# fx3_b.net
KiCad netlist of a schematic drawn in Altium Designer
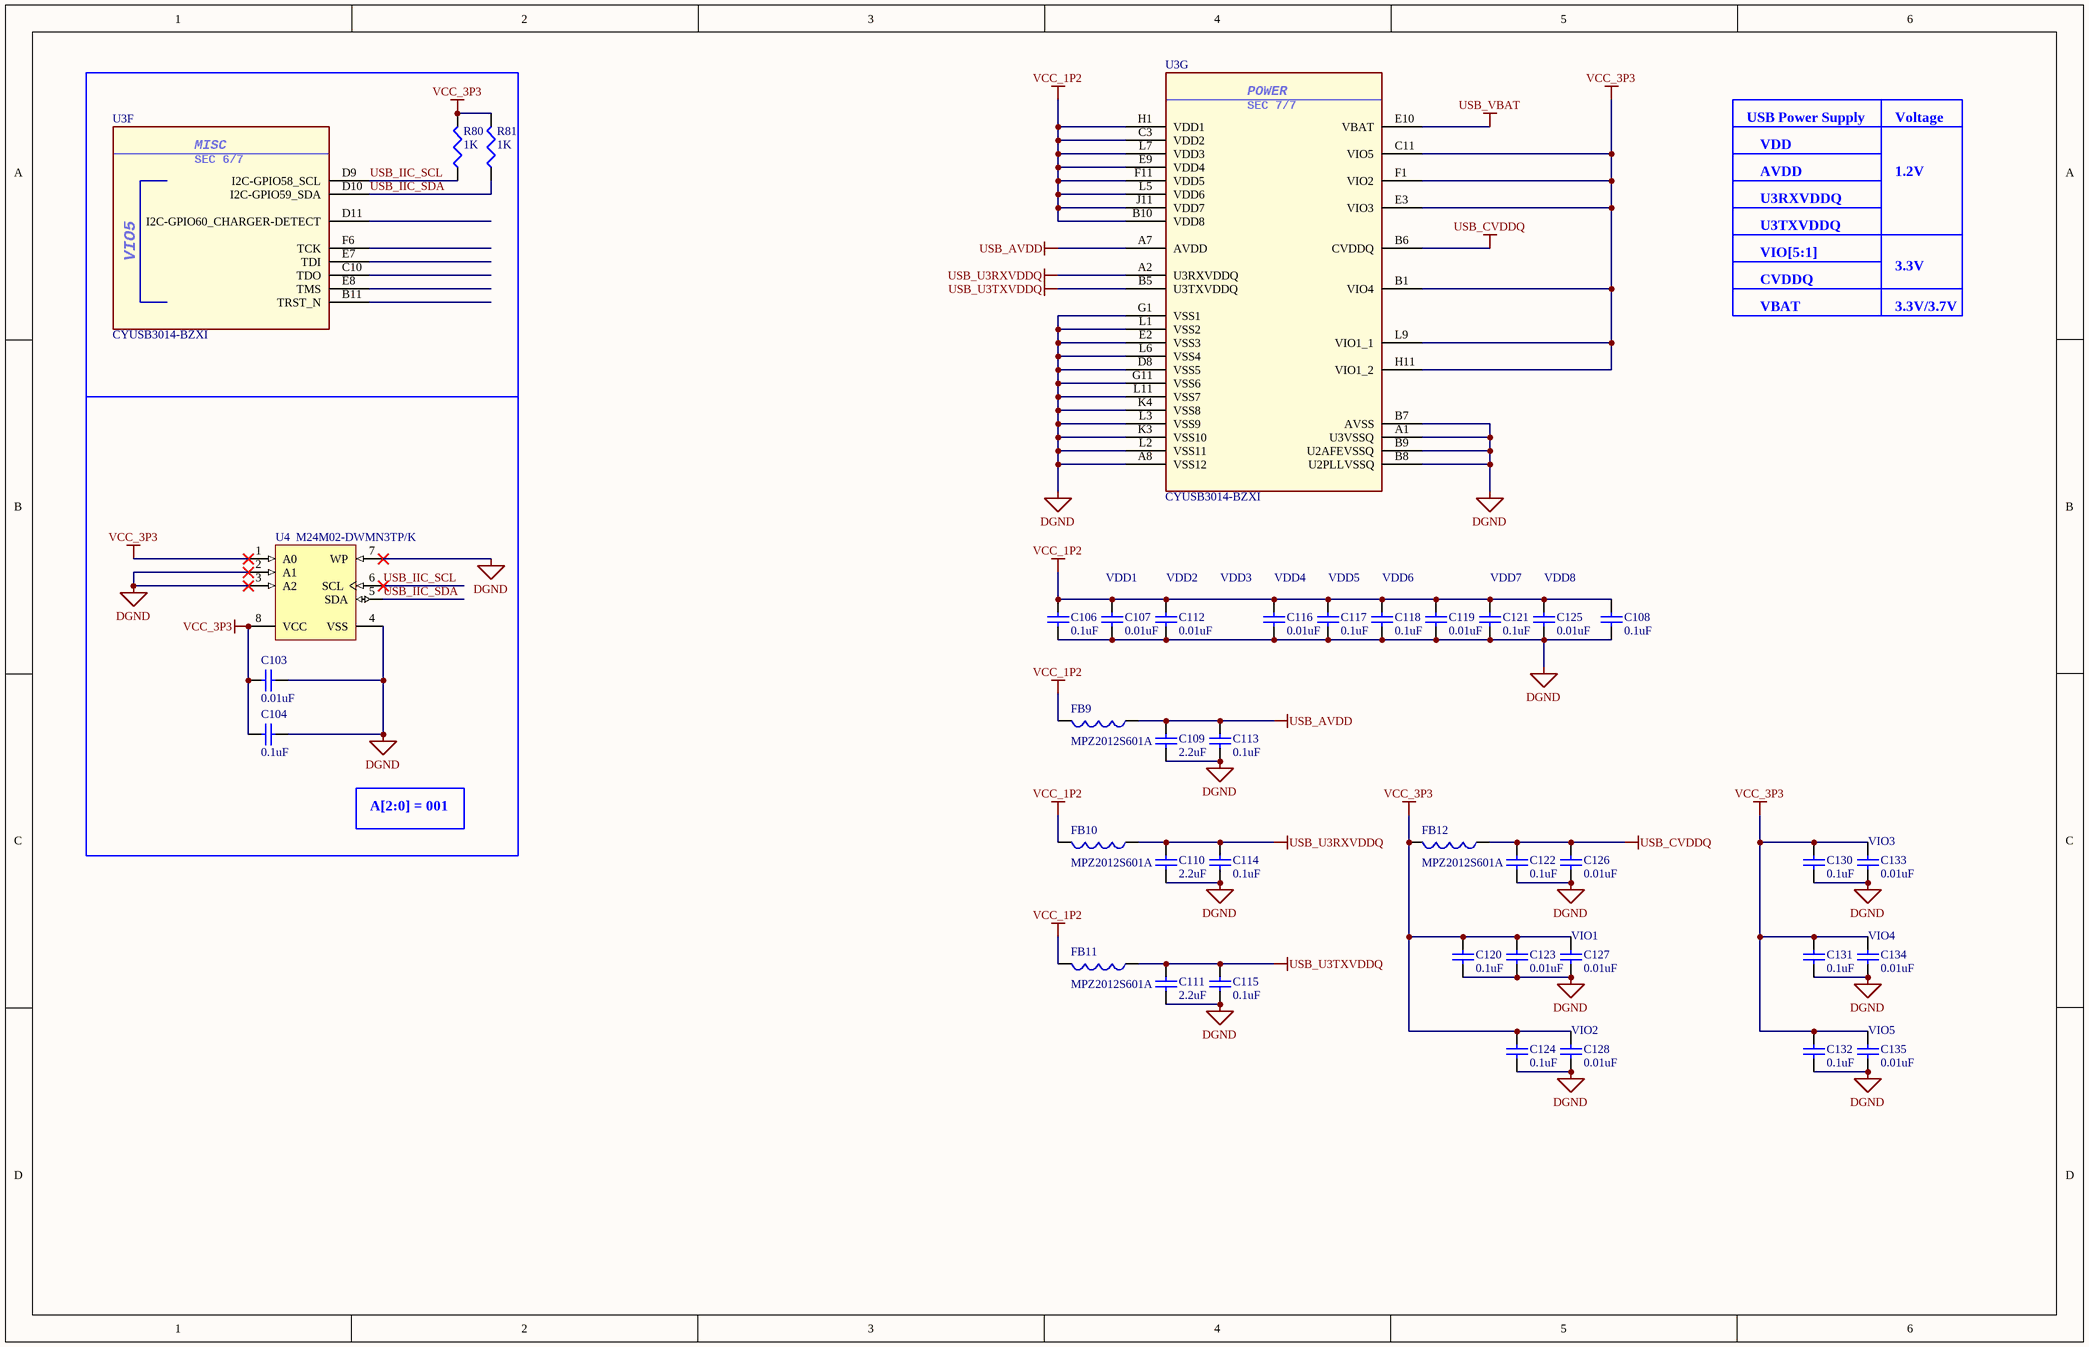
[diagram p0: fx3_b.SchDoc]

(export (version "E")
  (design (tool "Eeschema 10.0.6"))
  (components
    (comp (ref "C103")
      (value "0.01uF")
      (footprint "C_0402")
      (description "Capacitor (Semiconductor SIM Model)")
      (fields (field (name "Comment") "Capacitor") (field (name "PUBLISHER") "Altium Limited"))
      (libsource (lib "Miscellaneous Devices") (part "Cap Semi"))
    )
    (comp (ref "C104")
      (value "0.1uF")
      (footprint "C_0402")
      (description "Capacitor (Semiconductor SIM Model)")
      (fields (field (name "Comment") "Capacitor") (field (name "PUBLISHER") "Altium Limited"))
      (libsource (lib "Miscellaneous Devices") (part "Cap Semi"))
    )
    (comp (ref "C106")
      (value "0.1uF")
      (footprint "C_0402")
      (description "Capacitor (Semiconductor SIM Model)")
      (fields (field (name "Comment") "Capacitor") (field (name "PUBLISHER") "Altium Limited"))
      (libsource (lib "Miscellaneous Devices") (part "Cap Semi"))
    )
    (comp (ref "C107")
      (value "0.01uF")
      (footprint "C_0402")
      (description "Capacitor (Semiconductor SIM Model)")
      (fields (field (name "Comment") "Capacitor") (field (name "PUBLISHER") "Altium Limited"))
      (libsource (lib "Miscellaneous Devices") (part "Cap Semi"))
    )
    (comp (ref "C108")
      (value "0.1uF")
      (footprint "C_0402")
      (description "Capacitor (Semiconductor SIM Model)")
      (fields (field (name "Comment") "Capacitor") (field (name "PUBLISHER") "Altium Limited"))
      (libsource (lib "Miscellaneous Devices") (part "Cap Semi"))
    )
    (comp (ref "C109")
      (value "2.2uF")
      (footprint "C_0402")
      (description "Capacitor (Semiconductor SIM Model)")
      (fields (field (name "Comment") "Capacitor") (field (name "PUBLISHER") "Altium Limited"))
      (libsource (lib "Miscellaneous Devices") (part "Cap Semi"))
    )
    (comp (ref "C110")
      (value "2.2uF")
      (footprint "C_0402")
      (description "Capacitor (Semiconductor SIM Model)")
      (fields (field (name "Comment") "Capacitor") (field (name "PUBLISHER") "Altium Limited"))
      (libsource (lib "Miscellaneous Devices") (part "Cap Semi"))
    )
    (comp (ref "C111")
      (value "2.2uF")
      (footprint "C_0402")
      (description "Capacitor (Semiconductor SIM Model)")
      (fields (field (name "Comment") "Capacitor") (field (name "PUBLISHER") "Altium Limited"))
      (libsource (lib "Miscellaneous Devices") (part "Cap Semi"))
    )
    (comp (ref "C112")
      (value "0.01uF")
      (footprint "C_0402")
      (description "Capacitor (Semiconductor SIM Model)")
      (fields (field (name "Comment") "Capacitor") (field (name "PUBLISHER") "Altium Limited"))
      (libsource (lib "Miscellaneous Devices") (part "Cap Semi"))
    )
    (comp (ref "C113")
      (value "0.1uF")
      (footprint "C_0402")
      (description "Capacitor (Semiconductor SIM Model)")
      (fields (field (name "Comment") "Capacitor") (field (name "PUBLISHER") "Altium Limited"))
      (libsource (lib "Miscellaneous Devices") (part "Cap Semi"))
    )
    (comp (ref "C114")
      (value "0.1uF")
      (footprint "C_0402")
      (description "Capacitor (Semiconductor SIM Model)")
      (fields (field (name "Comment") "Capacitor") (field (name "PUBLISHER") "Altium Limited"))
      (libsource (lib "Miscellaneous Devices") (part "Cap Semi"))
    )
    (comp (ref "C115")
      (value "0.1uF")
      (footprint "C_0402")
      (description "Capacitor (Semiconductor SIM Model)")
      (fields (field (name "Comment") "Capacitor") (field (name "PUBLISHER") "Altium Limited"))
      (libsource (lib "Miscellaneous Devices") (part "Cap Semi"))
    )
    (comp (ref "C116")
      (value "0.01uF")
      (footprint "C_0402")
      (description "Capacitor (Semiconductor SIM Model)")
      (fields (field (name "Comment") "Capacitor") (field (name "PUBLISHER") "Altium Limited"))
      (libsource (lib "Miscellaneous Devices") (part "Cap Semi"))
    )
    (comp (ref "C117")
      (value "0.1uF")
      (footprint "C_0402")
      (description "Capacitor (Semiconductor SIM Model)")
      (fields (field (name "Comment") "Capacitor") (field (name "PUBLISHER") "Altium Limited"))
      (libsource (lib "Miscellaneous Devices") (part "Cap Semi"))
    )
    (comp (ref "C118")
      (value "0.1uF")
      (footprint "C_0402")
      (description "Capacitor (Semiconductor SIM Model)")
      (fields (field (name "Comment") "Capacitor") (field (name "PUBLISHER") "Altium Limited"))
      (libsource (lib "Miscellaneous Devices") (part "Cap Semi"))
    )
    (comp (ref "C119")
      (value "0.01uF")
      (footprint "C_0402")
      (description "Capacitor (Semiconductor SIM Model)")
      (fields (field (name "Comment") "Capacitor") (field (name "PUBLISHER") "Altium Limited"))
      (libsource (lib "Miscellaneous Devices") (part "Cap Semi"))
    )
    (comp (ref "C120")
      (value "0.1uF")
      (footprint "C_0402")
      (description "Capacitor (Semiconductor SIM Model)")
      (fields (field (name "Comment") "Capacitor") (field (name "PUBLISHER") "Altium Limited"))
      (libsource (lib "Miscellaneous Devices") (part "Cap Semi"))
    )
    (comp (ref "C121")
      (value "0.1uF")
      (footprint "C_0402")
      (description "Capacitor (Semiconductor SIM Model)")
      (fields (field (name "Comment") "Capacitor") (field (name "PUBLISHER") "Altium Limited"))
      (libsource (lib "Miscellaneous Devices") (part "Cap Semi"))
    )
    (comp (ref "C122")
      (value "0.1uF")
      (footprint "C_0402")
      (description "Capacitor (Semiconductor SIM Model)")
      (fields (field (name "Comment") "Capacitor") (field (name "PUBLISHER") "Altium Limited"))
      (libsource (lib "Miscellaneous Devices") (part "Cap Semi"))
    )
    (comp (ref "C123")
      (value "0.01uF")
      (footprint "C_0402")
      (description "Capacitor (Semiconductor SIM Model)")
      (fields (field (name "Comment") "Capacitor") (field (name "PUBLISHER") "Altium Limited"))
      (libsource (lib "Miscellaneous Devices") (part "Cap Semi"))
    )
    (comp (ref "C124")
      (value "0.1uF")
      (footprint "C_0402")
      (description "Capacitor (Semiconductor SIM Model)")
      (fields (field (name "Comment") "Capacitor") (field (name "PUBLISHER") "Altium Limited"))
      (libsource (lib "Miscellaneous Devices") (part "Cap Semi"))
    )
    (comp (ref "C125")
      (value "0.01uF")
      (footprint "C_0402")
      (description "Capacitor (Semiconductor SIM Model)")
      (fields (field (name "Comment") "Capacitor") (field (name "PUBLISHER") "Altium Limited"))
      (libsource (lib "Miscellaneous Devices") (part "Cap Semi"))
    )
    (comp (ref "C126")
      (value "0.01uF")
      (footprint "C_0402")
      (description "Capacitor (Semiconductor SIM Model)")
      (fields (field (name "Comment") "Capacitor") (field (name "PUBLISHER") "Altium Limited"))
      (libsource (lib "Miscellaneous Devices") (part "Cap Semi"))
    )
    (comp (ref "C127")
      (value "0.01uF")
      (footprint "C_0402")
      (description "Capacitor (Semiconductor SIM Model)")
      (fields (field (name "Comment") "Capacitor") (field (name "PUBLISHER") "Altium Limited"))
      (libsource (lib "Miscellaneous Devices") (part "Cap Semi"))
    )
    (comp (ref "C128")
      (value "0.01uF")
      (footprint "C_0402")
      (description "Capacitor (Semiconductor SIM Model)")
      (fields (field (name "Comment") "Capacitor") (field (name "PUBLISHER") "Altium Limited"))
      (libsource (lib "Miscellaneous Devices") (part "Cap Semi"))
    )
    (comp (ref "C130")
      (value "0.1uF")
      (footprint "C_0402")
      (description "Capacitor (Semiconductor SIM Model)")
      (fields (field (name "Comment") "Capacitor") (field (name "PUBLISHER") "Altium Limited"))
      (libsource (lib "Miscellaneous Devices") (part "Cap Semi"))
    )
    (comp (ref "C131")
      (value "0.1uF")
      (footprint "C_0402")
      (description "Capacitor (Semiconductor SIM Model)")
      (fields (field (name "Comment") "Capacitor") (field (name "PUBLISHER") "Altium Limited"))
      (libsource (lib "Miscellaneous Devices") (part "Cap Semi"))
    )
    (comp (ref "C132")
      (value "0.1uF")
      (footprint "C_0402")
      (description "Capacitor (Semiconductor SIM Model)")
      (fields (field (name "Comment") "Capacitor") (field (name "PUBLISHER") "Altium Limited"))
      (libsource (lib "Miscellaneous Devices") (part "Cap Semi"))
    )
    (comp (ref "C133")
      (value "0.01uF")
      (footprint "C_0402")
      (description "Capacitor (Semiconductor SIM Model)")
      (fields (field (name "Comment") "Capacitor") (field (name "PUBLISHER") "Altium Limited"))
      (libsource (lib "Miscellaneous Devices") (part "Cap Semi"))
    )
    (comp (ref "C134")
      (value "0.01uF")
      (footprint "C_0402")
      (description "Capacitor (Semiconductor SIM Model)")
      (fields (field (name "Comment") "Capacitor") (field (name "PUBLISHER") "Altium Limited"))
      (libsource (lib "Miscellaneous Devices") (part "Cap Semi"))
    )
    (comp (ref "C135")
      (value "0.01uF")
      (footprint "C_0402")
      (description "Capacitor (Semiconductor SIM Model)")
      (fields (field (name "Comment") "Capacitor") (field (name "PUBLISHER") "Altium Limited"))
      (libsource (lib "Miscellaneous Devices") (part "Cap Semi"))
    )
    (comp (ref "FB9")
      (value "MPZ2012S601A")
      (footprint "SMD_0805")
      (description "MPZ2012X")
      (libsource (lib "clc_ad_pro") (part "MPZ2012X"))
    )
    (comp (ref "FB10")
      (value "MPZ2012S601A")
      (footprint "SMD_0805")
      (description "MPZ2012X")
      (libsource (lib "clc_ad_pro") (part "MPZ2012X"))
    )
    (comp (ref "FB11")
      (value "MPZ2012S601A")
      (footprint "SMD_0805")
      (description "MPZ2012X")
      (libsource (lib "clc_ad_pro") (part "MPZ2012X"))
    )
    (comp (ref "FB12")
      (value "MPZ2012S601A")
      (footprint "SMD_0805")
      (description "MPZ2012X")
      (libsource (lib "clc_ad_pro") (part "MPZ2012X"))
    )
    (comp (ref "R80")
      (value "1K")
      (footprint "J1-0603")
      (description "Resistor")
      (fields (field (name "PUBLISHER") "Altium Limited"))
      (libsource (lib "Miscellaneous Devices") (part "Res3"))
    )
    (comp (ref "R81")
      (value "1K")
      (footprint "J1-0603")
      (description "Resistor")
      (fields (field (name "PUBLISHER") "Altium Limited"))
      (libsource (lib "Miscellaneous Devices") (part "Res3"))
    )
    (comp (ref "U3")
      (value "CYUSB3014-BZXI")
      (footprint "CYUSB301X_BGA121x11")
      (description "FX3 CYUSB3014")
      (libsource (lib "apex_usb_v2") (part "CYUSB30XX"))
    )
    (comp (ref "U4")
      (value "M24M02-DWMN3TP/K")
      (footprint "SOIC-SN8_N")
      (description "256Kbit, 400kHz, 2.5V, I2C Serial EEPROM, 8-Pin SOIC 150mil, Industrial Temperature")
      (fields (field (name "MANUFACTURER") "Microchip") (field (name "PARTNUMBER") "24LC256-I/SN"))
      (libsource (lib "Microchip I2C Serial EEPROM") (part "24LC256-I/SN"))
    )
  )
  (nets
    (net (code "1") (name "/USB_IIC_SCL") (class "Default")
      (node (ref "R80") (pin "1") (pinfunction "1_1") (pintype "passive"))
      (node (ref "U3") (pin "D9") (pinfunction "I2C-GPIO58_SCL_D9") (pintype "passive"))
      (node (ref "U4") (pin "6") (pinfunction "SCL_6") (pintype "input"))
    )
    (net (code "2") (name "/USB_IIC_SDA") (class "Default")
      (node (ref "R81") (pin "1") (pinfunction "1_1") (pintype "passive"))
      (node (ref "U3") (pin "D10") (pinfunction "I2C-GPIO59_SDA_D10") (pintype "passive"))
      (node (ref "U4") (pin "5") (pinfunction "SDA_5") (pintype "bidirectional"))
    )
    (net (code "3") (name "DGND") (class "Default")
      (node (ref "C103") (pin "2") (pinfunction "2_2") (pintype "passive"))
      (node (ref "C104") (pin "2") (pinfunction "2_2") (pintype "passive"))
      (node (ref "C106") (pin "2") (pinfunction "2_2") (pintype "passive"))
      (node (ref "C107") (pin "2") (pinfunction "2_2") (pintype "passive"))
      (node (ref "C108") (pin "2") (pinfunction "2_2") (pintype "passive"))
      (node (ref "C109") (pin "2") (pinfunction "2_2") (pintype "passive"))
      (node (ref "C110") (pin "2") (pinfunction "2_2") (pintype "passive"))
      (node (ref "C111") (pin "2") (pinfunction "2_2") (pintype "passive"))
      (node (ref "C112") (pin "2") (pinfunction "2_2") (pintype "passive"))
      (node (ref "C113") (pin "2") (pinfunction "2_2") (pintype "passive"))
      (node (ref "C114") (pin "2") (pinfunction "2_2") (pintype "passive"))
      (node (ref "C115") (pin "2") (pinfunction "2_2") (pintype "passive"))
      (node (ref "C116") (pin "2") (pinfunction "2_2") (pintype "passive"))
      (node (ref "C117") (pin "2") (pinfunction "2_2") (pintype "passive"))
      (node (ref "C118") (pin "2") (pinfunction "2_2") (pintype "passive"))
      (node (ref "C119") (pin "2") (pinfunction "2_2") (pintype "passive"))
      (node (ref "C120") (pin "2") (pinfunction "2_2") (pintype "passive"))
      (node (ref "C121") (pin "2") (pinfunction "2_2") (pintype "passive"))
      (node (ref "C122") (pin "2") (pinfunction "2_2") (pintype "passive"))
      (node (ref "C123") (pin "2") (pinfunction "2_2") (pintype "passive"))
      (node (ref "C124") (pin "2") (pinfunction "2_2") (pintype "passive"))
      (node (ref "C125") (pin "2") (pinfunction "2_2") (pintype "passive"))
      (node (ref "C126") (pin "2") (pinfunction "2_2") (pintype "passive"))
      (node (ref "C127") (pin "2") (pinfunction "2_2") (pintype "passive"))
      (node (ref "C128") (pin "2") (pinfunction "2_2") (pintype "passive"))
      (node (ref "C130") (pin "2") (pinfunction "2_2") (pintype "passive"))
      (node (ref "C131") (pin "2") (pinfunction "2_2") (pintype "passive"))
      (node (ref "C132") (pin "2") (pinfunction "2_2") (pintype "passive"))
      (node (ref "C133") (pin "2") (pinfunction "2_2") (pintype "passive"))
      (node (ref "C134") (pin "2") (pinfunction "2_2") (pintype "passive"))
      (node (ref "C135") (pin "2") (pinfunction "2_2") (pintype "passive"))
      (node (ref "U3") (pin "A1") (pinfunction "U3VSSQ_A1") (pintype "passive"))
      (node (ref "U3") (pin "A8") (pinfunction "VSS12_A8") (pintype "passive"))
      (node (ref "U3") (pin "B7") (pinfunction "AVSS_B7") (pintype "passive"))
      (node (ref "U3") (pin "B8") (pinfunction "U2PLLVSSQ_B8") (pintype "passive"))
      (node (ref "U3") (pin "B9") (pinfunction "U2AFEVSSQ_B9") (pintype "passive"))
      (node (ref "U3") (pin "D8") (pinfunction "VSS5_D8") (pintype "passive"))
      (node (ref "U3") (pin "E2") (pinfunction "VSS3_E2") (pintype "passive"))
      (node (ref "U3") (pin "G1") (pinfunction "VSS1_G1") (pintype "passive"))
      (node (ref "U3") (pin "G11") (pinfunction "VSS6_G11") (pintype "passive"))
      (node (ref "U3") (pin "K3") (pinfunction "VSS10_K3") (pintype "passive"))
      (node (ref "U3") (pin "K4") (pinfunction "VSS8_K4") (pintype "passive"))
      (node (ref "U3") (pin "L1") (pinfunction "VSS2_L1") (pintype "passive"))
      (node (ref "U3") (pin "L11") (pinfunction "VSS7_L11") (pintype "passive"))
      (node (ref "U3") (pin "L2") (pinfunction "VSS11_L2") (pintype "passive"))
      (node (ref "U3") (pin "L3") (pinfunction "VSS9_L3") (pintype "passive"))
      (node (ref "U3") (pin "L6") (pinfunction "VSS4_L6") (pintype "passive"))
      (node (ref "U4") (pin "2") (pinfunction "A1_2") (pintype "input"))
      (node (ref "U4") (pin "3") (pinfunction "A2_3") (pintype "input"))
      (node (ref "U4") (pin "4") (pinfunction "VSS_4") (pintype "power_in"))
      (node (ref "U4") (pin "7") (pinfunction "WP_7") (pintype "input"))
    )
    (net (code "4") (name "USB_AVDD") (class "Default")
      (node (ref "C109") (pin "1") (pinfunction "1_1") (pintype "passive"))
      (node (ref "C113") (pin "1") (pinfunction "1_1") (pintype "passive"))
      (node (ref "FB9") (pin "1") (pinfunction "1_1") (pintype "passive"))
      (node (ref "U3") (pin "A7") (pinfunction "AVDD_A7") (pintype "passive"))
    )
    (net (code "5") (name "USB_CVDDQ") (class "Default")
      (node (ref "C122") (pin "1") (pinfunction "1_1") (pintype "passive"))
      (node (ref "C126") (pin "1") (pinfunction "1_1") (pintype "passive"))
      (node (ref "FB12") (pin "1") (pinfunction "1_1") (pintype "passive"))
      (node (ref "U3") (pin "B6") (pinfunction "CVDDQ_B6") (pintype "passive"))
    )
    (net (code "6") (name "USB_U3RXVDDQ") (class "Default")
      (node (ref "C110") (pin "1") (pinfunction "1_1") (pintype "passive"))
      (node (ref "C114") (pin "1") (pinfunction "1_1") (pintype "passive"))
      (node (ref "FB10") (pin "1") (pinfunction "1_1") (pintype "passive"))
      (node (ref "U3") (pin "A2") (pinfunction "U3RXVDDQ_A2") (pintype "passive"))
    )
    (net (code "7") (name "USB_U3TXVDDQ") (class "Default")
      (node (ref "C111") (pin "1") (pinfunction "1_1") (pintype "passive"))
      (node (ref "C115") (pin "1") (pinfunction "1_1") (pintype "passive"))
      (node (ref "FB11") (pin "1") (pinfunction "1_1") (pintype "passive"))
      (node (ref "U3") (pin "B5") (pinfunction "U3TXVDDQ_B5") (pintype "passive"))
    )
    (net (code "8") (name "USB_VBAT") (class "Default")
      (node (ref "U3") (pin "E10") (pinfunction "VBAT_E10") (pintype "passive"))
    )
    (net (code "9") (name "VCC_1P2") (class "Default")
      (node (ref "C106") (pin "1") (pinfunction "1_1") (pintype "passive"))
      (node (ref "C107") (pin "1") (pinfunction "1_1") (pintype "passive"))
      (node (ref "C108") (pin "1") (pinfunction "1_1") (pintype "passive"))
      (node (ref "C112") (pin "1") (pinfunction "1_1") (pintype "passive"))
      (node (ref "C116") (pin "1") (pinfunction "1_1") (pintype "passive"))
      (node (ref "C117") (pin "1") (pinfunction "1_1") (pintype "passive"))
      (node (ref "C118") (pin "1") (pinfunction "1_1") (pintype "passive"))
      (node (ref "C119") (pin "1") (pinfunction "1_1") (pintype "passive"))
      (node (ref "C121") (pin "1") (pinfunction "1_1") (pintype "passive"))
      (node (ref "C125") (pin "1") (pinfunction "1_1") (pintype "passive"))
      (node (ref "FB10") (pin "2") (pinfunction "2_2") (pintype "passive"))
      (node (ref "FB11") (pin "2") (pinfunction "2_2") (pintype "passive"))
      (node (ref "FB9") (pin "2") (pinfunction "2_2") (pintype "passive"))
      (node (ref "U3") (pin "B10") (pinfunction "VDD8_B10") (pintype "passive"))
      (node (ref "U3") (pin "C3") (pinfunction "VDD2_C3") (pintype "passive"))
      (node (ref "U3") (pin "E9") (pinfunction "VDD4_E9") (pintype "passive"))
      (node (ref "U3") (pin "F11") (pinfunction "VDD5_F11") (pintype "passive"))
      (node (ref "U3") (pin "H1") (pinfunction "VDD1_H1") (pintype "passive"))
      (node (ref "U3") (pin "J11") (pinfunction "VDD7_J11") (pintype "passive"))
      (node (ref "U3") (pin "L5") (pinfunction "VDD6_L5") (pintype "passive"))
      (node (ref "U3") (pin "L7") (pinfunction "VDD3_L7") (pintype "passive"))
    )
    (net (code "10") (name "VCC_3P3") (class "Default")
      (node (ref "C103") (pin "1") (pinfunction "1_1") (pintype "passive"))
      (node (ref "C104") (pin "1") (pinfunction "1_1") (pintype "passive"))
      (node (ref "C120") (pin "1") (pinfunction "1_1") (pintype "passive"))
      (node (ref "C123") (pin "1") (pinfunction "1_1") (pintype "passive"))
      (node (ref "C124") (pin "1") (pinfunction "1_1") (pintype "passive"))
      (node (ref "C127") (pin "1") (pinfunction "1_1") (pintype "passive"))
      (node (ref "C128") (pin "1") (pinfunction "1_1") (pintype "passive"))
      (node (ref "C130") (pin "1") (pinfunction "1_1") (pintype "passive"))
      (node (ref "C131") (pin "1") (pinfunction "1_1") (pintype "passive"))
      (node (ref "C132") (pin "1") (pinfunction "1_1") (pintype "passive"))
      (node (ref "C133") (pin "1") (pinfunction "1_1") (pintype "passive"))
      (node (ref "C134") (pin "1") (pinfunction "1_1") (pintype "passive"))
      (node (ref "C135") (pin "1") (pinfunction "1_1") (pintype "passive"))
      (node (ref "FB12") (pin "2") (pinfunction "2_2") (pintype "passive"))
      (node (ref "R80") (pin "2") (pinfunction "2_2") (pintype "passive"))
      (node (ref "R81") (pin "2") (pinfunction "2_2") (pintype "passive"))
      (node (ref "U3") (pin "B1") (pinfunction "VIO4_B1") (pintype "passive"))
      (node (ref "U3") (pin "C11") (pinfunction "VIO5_C11") (pintype "passive"))
      (node (ref "U3") (pin "E3") (pinfunction "VIO3_E3") (pintype "passive"))
      (node (ref "U3") (pin "F1") (pinfunction "VIO2_F1") (pintype "passive"))
      (node (ref "U3") (pin "H11") (pinfunction "VIO1_2_H11") (pintype "passive"))
      (node (ref "U3") (pin "L9") (pinfunction "VIO1_1_L9") (pintype "passive"))
      (node (ref "U4") (pin "1") (pinfunction "A0_1") (pintype "input"))
      (node (ref "U4") (pin "8") (pinfunction "VCC_8") (pintype "power_in"))
    )
    (net (code "11") (name "unconnected-(U3F-I2C-GPIO60_CHARGER-DETECT-PadD11)") (class "Default")
      (node (ref "U3") (pin "D11") (pinfunction "I2C-GPIO60_CHARGER-DETECT_D11") (pintype "passive"))
    )
    (net (code "12") (name "unconnected-(U3F-TCK-PadF6)") (class "Default")
      (node (ref "U3") (pin "F6") (pinfunction "TCK_F6") (pintype "passive"))
    )
    (net (code "13") (name "unconnected-(U3F-TDI-PadE7)") (class "Default")
      (node (ref "U3") (pin "E7") (pinfunction "TDI_E7") (pintype "passive"))
    )
    (net (code "14") (name "unconnected-(U3F-TDO-PadC10)") (class "Default")
      (node (ref "U3") (pin "C10") (pinfunction "TDO_C10") (pintype "passive"))
    )
    (net (code "15") (name "unconnected-(U3F-TMS-PadE8)") (class "Default")
      (node (ref "U3") (pin "E8") (pinfunction "TMS_E8") (pintype "passive"))
    )
    (net (code "16") (name "unconnected-(U3F-TRST_N-PadB11)") (class "Default")
      (node (ref "U3") (pin "B11") (pinfunction "TRST_N_B11") (pintype "passive"))
    )
  )
)
